# base_plate_noisy_crickets.net
KiCad netlist of a schematic drawn in EAGLE
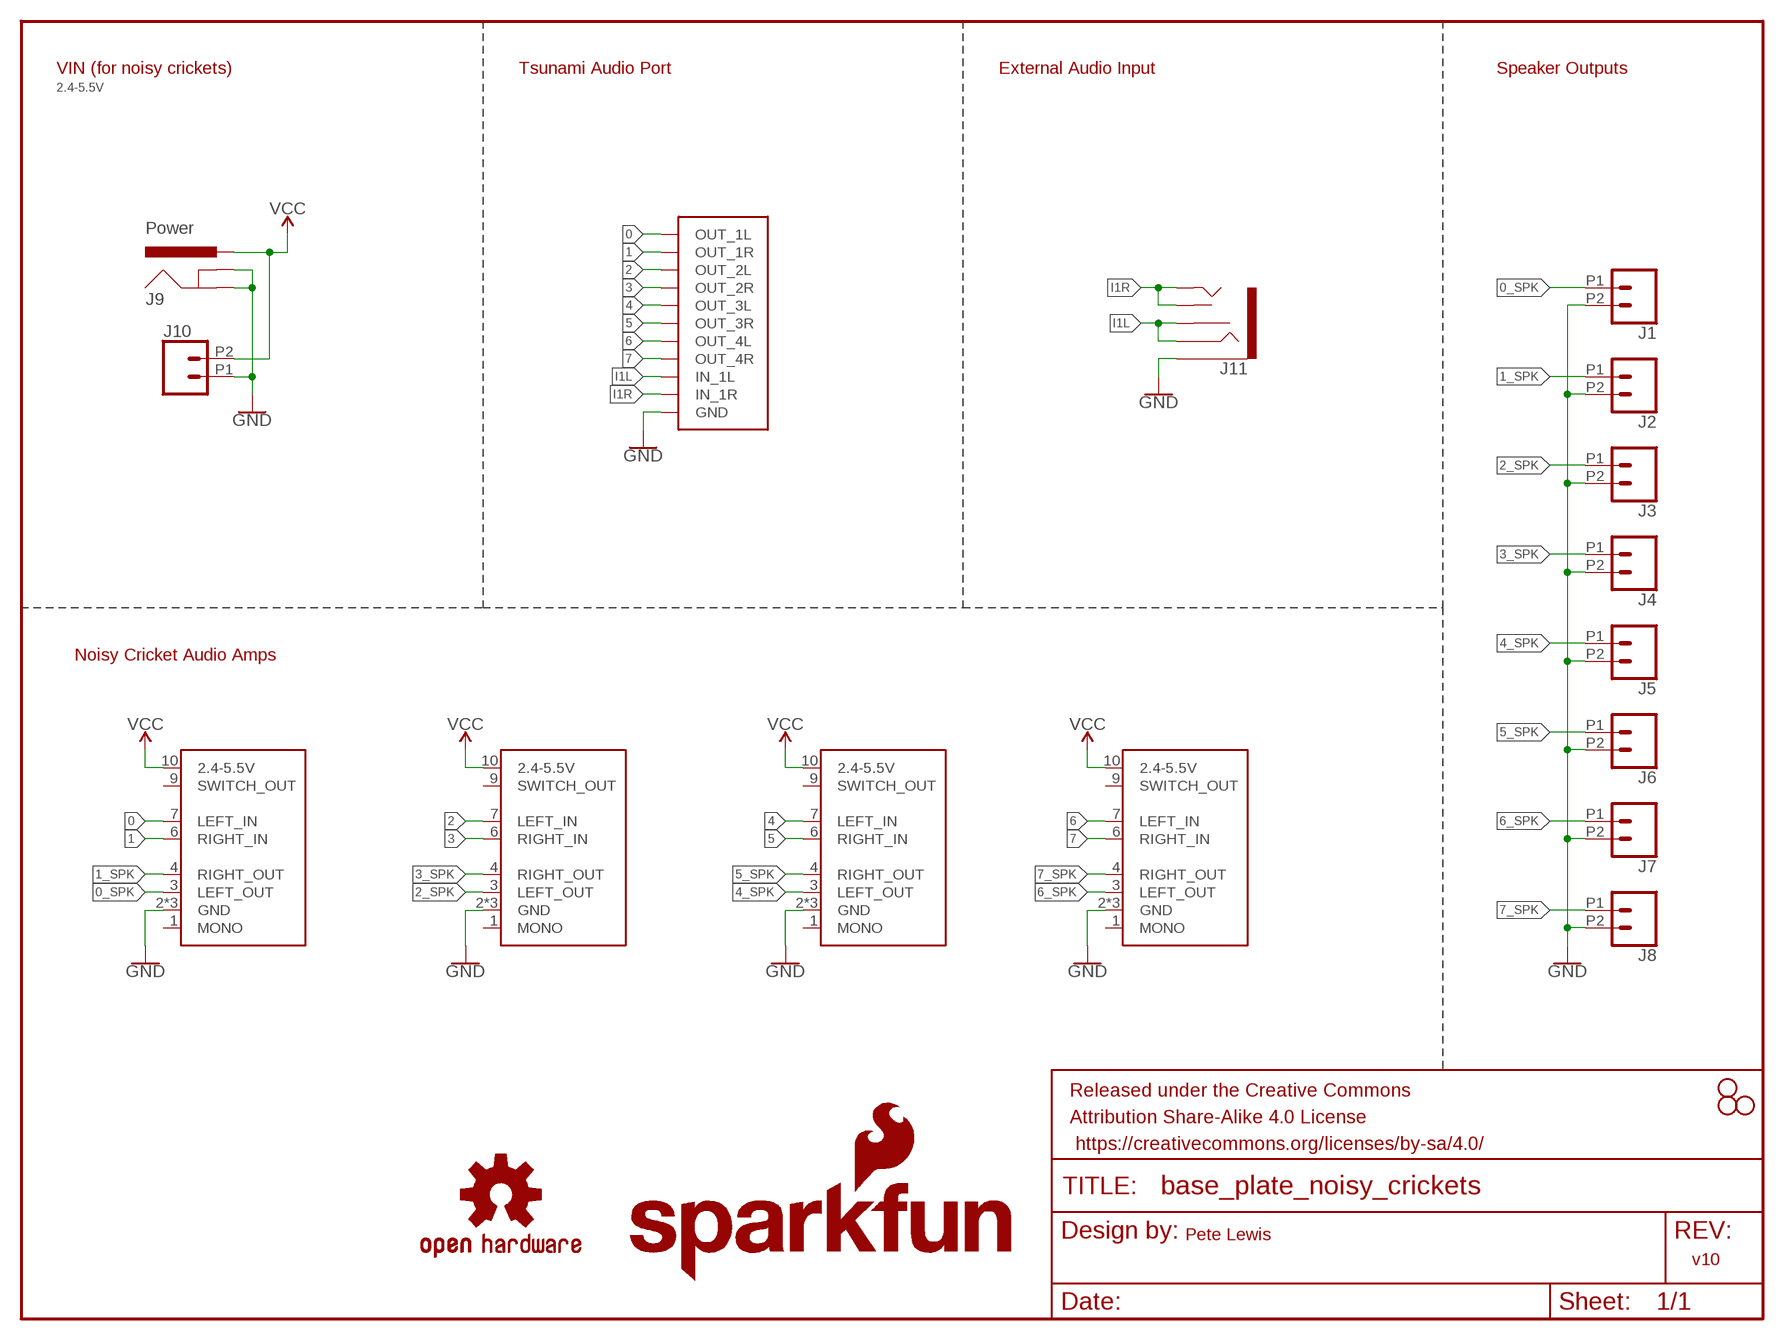
[diagram p0: schematic, sheet 1]

(export (version "E")
  (design (tool "Eeschema 10.0.6"))
  (components
    (comp (ref "FRAME1")
      (value "FRAME-LETTER")
      (footprint "eagle-import:CREATIVE_COMMONS")
      (libsource (lib "eagle-import") (part "FRAME-LETTER"))
    )
    (comp (ref "H1")
      (value "STAND-OFFTIGHT")
      (footprint "eagle-import:STAND-OFF-TIGHT")
      (libsource (lib "eagle-import") (part "STAND-OFFTIGHT"))
    )
    (comp (ref "H3")
      (value "STAND-OFFTIGHT")
      (footprint "eagle-import:STAND-OFF-TIGHT")
      (libsource (lib "eagle-import") (part "STAND-OFFTIGHT"))
    )
    (comp (ref "H4")
      (value "STAND-OFFTIGHT")
      (footprint "eagle-import:STAND-OFF-TIGHT")
      (libsource (lib "eagle-import") (part "STAND-OFFTIGHT"))
    )
    (comp (ref "J1")
      (value "CONN_022.54MM_SCREWTERM")
      (footprint "eagle-import:1X02_2.54_SCREWTERM")
      (libsource (lib "eagle-import") (part "CONN_022.54MM_SCREWTERM"))
    )
    (comp (ref "J2")
      (value "CONN_022.54MM_SCREWTERM")
      (footprint "eagle-import:1X02_2.54_SCREWTERM")
      (libsource (lib "eagle-import") (part "CONN_022.54MM_SCREWTERM"))
    )
    (comp (ref "J3")
      (value "CONN_022.54MM_SCREWTERM")
      (footprint "eagle-import:1X02_2.54_SCREWTERM")
      (libsource (lib "eagle-import") (part "CONN_022.54MM_SCREWTERM"))
    )
    (comp (ref "J4")
      (value "CONN_022.54MM_SCREWTERM")
      (footprint "eagle-import:1X02_2.54_SCREWTERM")
      (libsource (lib "eagle-import") (part "CONN_022.54MM_SCREWTERM"))
    )
    (comp (ref "J5")
      (value "CONN_022.54MM_SCREWTERM")
      (footprint "eagle-import:1X02_2.54_SCREWTERM")
      (libsource (lib "eagle-import") (part "CONN_022.54MM_SCREWTERM"))
    )
    (comp (ref "J6")
      (value "CONN_022.54MM_SCREWTERM")
      (footprint "eagle-import:1X02_2.54_SCREWTERM")
      (libsource (lib "eagle-import") (part "CONN_022.54MM_SCREWTERM"))
    )
    (comp (ref "J7")
      (value "CONN_022.54MM_SCREWTERM")
      (footprint "eagle-import:1X02_2.54_SCREWTERM")
      (libsource (lib "eagle-import") (part "CONN_022.54MM_SCREWTERM"))
    )
    (comp (ref "J8")
      (value "CONN_022.54MM_SCREWTERM")
      (footprint "eagle-import:1X02_2.54_SCREWTERM")
      (libsource (lib "eagle-import") (part "CONN_022.54MM_SCREWTERM"))
    )
    (comp (ref "J9")
      (value "Power")
      (footprint "eagle-import:POWER_JACK_PTH_LOCK")
      (libsource (lib "eagle-import") (part "POWER_JACKPTH_LOCK"))
    )
    (comp (ref "J10")
      (value "CONN_022.54MM_SCREWTERM")
      (footprint "eagle-import:1X02_2.54_SCREWTERM")
      (libsource (lib "eagle-import") (part "CONN_022.54MM_SCREWTERM"))
    )
    (comp (ref "J11")
      (value "AUDIO_JACK_3.5MM_PTH")
      (footprint "eagle-import:AUDIO-JACK")
      (libsource (lib "eagle-import") (part "AUDIO_JACK_3.5MM_PTH"))
    )
    (comp (ref "LOGO1")
      (value "SFE_LOGO_NAME_FLAME.1_INCH")
      (footprint "eagle-import:SFE_LOGO_NAME_FLAME_.1")
      (libsource (lib "eagle-import") (part "SFE_LOGO_NAME_FLAME.1_INCH"))
    )
    (comp (ref "LOGO2")
      (value "OSHW-LOGOS")
      (footprint "eagle-import:OSHW-LOGO-S")
      (libsource (lib "eagle-import") (part "OSHW-LOGOS"))
    )
    (comp (ref "LOGO3")
      (value "SFE_LOGO_NAME_FLAME.3_INCH")
      (footprint "eagle-import:SFE_LOGO_NAME_FLAME_.3")
      (libsource (lib "eagle-import") (part "SFE_LOGO_NAME_FLAME.3_INCH"))
    )
    (comp (ref "U$1")
      (value "NOISY_CRICKET")
      (footprint "eagle-import:NOISY_CRICKET_W_PTH")
      (libsource (lib "eagle-import") (part "NOISY_CRICKET"))
    )
    (comp (ref "U$2")
      (value "NOISY_CRICKET")
      (footprint "eagle-import:NOISY_CRICKET_W_PTH")
      (libsource (lib "eagle-import") (part "NOISY_CRICKET"))
    )
    (comp (ref "U$3")
      (value "NOISY_CRICKET")
      (footprint "eagle-import:NOISY_CRICKET_W_PTH")
      (libsource (lib "eagle-import") (part "NOISY_CRICKET"))
    )
    (comp (ref "U$4")
      (value "NOISY_CRICKET")
      (footprint "eagle-import:NOISY_CRICKET_W_PTH")
      (libsource (lib "eagle-import") (part "NOISY_CRICKET"))
    )
    (comp (ref "U$5")
      (value "TSUNAMI_AUDIO_PORTS")
      (footprint "eagle-import:TSUNAMI_AUDIO_PORTS")
      (libsource (lib "eagle-import") (part "TSUNAMI_AUDIO_PORTS"))
    )
  )
  (nets
    (net (code "1") (name "0") (class "Default")
      (node (ref "U$1") (pin "7") (pinfunction "LEFT_IN_7") (pintype "bidirectional"))
      (node (ref "U$5") (pin "O1L") (pinfunction "OUT_1L_O1L") (pintype "bidirectional"))
    )
    (net (code "2") (name "0_SPK") (class "Default")
      (node (ref "J1") (pin "P1") (pinfunction "1_P1") (pintype "passive"))
      (node (ref "U$1") (pin "3") (pinfunction "LEFT_OUT_3") (pintype "bidirectional"))
    )
    (net (code "3") (name "1") (class "Default")
      (node (ref "U$1") (pin "6") (pinfunction "RIGHT_IN_6") (pintype "bidirectional"))
      (node (ref "U$5") (pin "O1R") (pinfunction "OUT_1R_O1R") (pintype "bidirectional"))
    )
    (net (code "4") (name "1_SPK") (class "Default")
      (node (ref "J2") (pin "P1") (pinfunction "1_P1") (pintype "passive"))
      (node (ref "U$1") (pin "4") (pinfunction "RIGHT_OUT_4") (pintype "bidirectional"))
    )
    (net (code "5") (name "2") (class "Default")
      (node (ref "U$2") (pin "7") (pinfunction "LEFT_IN_7") (pintype "bidirectional"))
      (node (ref "U$5") (pin "O2L") (pinfunction "OUT_2L_O2L") (pintype "bidirectional"))
    )
    (net (code "6") (name "2_SPK") (class "Default")
      (node (ref "J3") (pin "P1") (pinfunction "1_P1") (pintype "passive"))
      (node (ref "U$2") (pin "3") (pinfunction "LEFT_OUT_3") (pintype "bidirectional"))
    )
    (net (code "7") (name "3") (class "Default")
      (node (ref "U$2") (pin "6") (pinfunction "RIGHT_IN_6") (pintype "bidirectional"))
      (node (ref "U$5") (pin "O2R") (pinfunction "OUT_2R_O2R") (pintype "bidirectional"))
    )
    (net (code "8") (name "3_SPK") (class "Default")
      (node (ref "J4") (pin "P1") (pinfunction "1_P1") (pintype "passive"))
      (node (ref "U$2") (pin "4") (pinfunction "RIGHT_OUT_4") (pintype "bidirectional"))
    )
    (net (code "9") (name "4") (class "Default")
      (node (ref "U$3") (pin "7") (pinfunction "LEFT_IN_7") (pintype "bidirectional"))
      (node (ref "U$5") (pin "O3L") (pinfunction "OUT_3L_O3L") (pintype "bidirectional"))
    )
    (net (code "10") (name "4_SPK") (class "Default")
      (node (ref "J5") (pin "P1") (pinfunction "1_P1") (pintype "passive"))
      (node (ref "U$3") (pin "3") (pinfunction "LEFT_OUT_3") (pintype "bidirectional"))
    )
    (net (code "11") (name "5") (class "Default")
      (node (ref "U$3") (pin "6") (pinfunction "RIGHT_IN_6") (pintype "bidirectional"))
      (node (ref "U$5") (pin "O3R") (pinfunction "OUT_3R_O3R") (pintype "bidirectional"))
    )
    (net (code "12") (name "5_SPK") (class "Default")
      (node (ref "J6") (pin "P1") (pinfunction "1_P1") (pintype "passive"))
      (node (ref "U$3") (pin "4") (pinfunction "RIGHT_OUT_4") (pintype "bidirectional"))
    )
    (net (code "13") (name "6") (class "Default")
      (node (ref "U$4") (pin "7") (pinfunction "LEFT_IN_7") (pintype "bidirectional"))
      (node (ref "U$5") (pin "O4L") (pinfunction "OUT_4L_O4L") (pintype "bidirectional"))
    )
    (net (code "14") (name "6_SPK") (class "Default")
      (node (ref "J7") (pin "P1") (pinfunction "1_P1") (pintype "passive"))
      (node (ref "U$4") (pin "3") (pinfunction "LEFT_OUT_3") (pintype "bidirectional"))
    )
    (net (code "15") (name "7") (class "Default")
      (node (ref "U$4") (pin "6") (pinfunction "RIGHT_IN_6") (pintype "bidirectional"))
      (node (ref "U$5") (pin "O4R") (pinfunction "OUT_4R_O4R") (pintype "bidirectional"))
    )
    (net (code "16") (name "7_SPK") (class "Default")
      (node (ref "J8") (pin "P1") (pinfunction "1_P1") (pintype "passive"))
      (node (ref "U$4") (pin "4") (pinfunction "RIGHT_OUT_4") (pintype "bidirectional"))
    )
    (net (code "17") (name "GND") (class "Default")
      (node (ref "J1") (pin "P2") (pinfunction "2_P2") (pintype "passive"))
      (node (ref "J10") (pin "P1") (pinfunction "1_P1") (pintype "passive"))
      (node (ref "J11") (pin "SLEEVE") (pinfunction "SLEEVE_SLEEVE") (pintype "bidirectional"))
      (node (ref "J2") (pin "P2") (pinfunction "2_P2") (pintype "passive"))
      (node (ref "J3") (pin "P2") (pinfunction "2_P2") (pintype "passive"))
      (node (ref "J4") (pin "P2") (pinfunction "2_P2") (pintype "passive"))
      (node (ref "J5") (pin "P2") (pinfunction "2_P2") (pintype "passive"))
      (node (ref "J6") (pin "P2") (pinfunction "2_P2") (pintype "passive"))
      (node (ref "J7") (pin "P2") (pinfunction "2_P2") (pintype "passive"))
      (node (ref "J8") (pin "P2") (pinfunction "2_P2") (pintype "passive"))
      (node (ref "J9") (pin "GND") (pinfunction "GND_GND") (pintype "bidirectional"))
      (node (ref "J9") (pin "GNDBREAK") (pinfunction "GNDBREAK_GNDBREAK") (pintype "bidirectional"))
      (node (ref "U$1") (pin "2") (pinfunction "GND_2") (pintype "bidirectional"))
      (node (ref "U$1") (pin "5") (pinfunction "GND_5") (pintype "bidirectional"))
      (node (ref "U$1") (pin "8") (pinfunction "GND_8") (pintype "bidirectional"))
      (node (ref "U$2") (pin "2") (pinfunction "GND_2") (pintype "bidirectional"))
      (node (ref "U$2") (pin "5") (pinfunction "GND_5") (pintype "bidirectional"))
      (node (ref "U$2") (pin "8") (pinfunction "GND_8") (pintype "bidirectional"))
      (node (ref "U$3") (pin "2") (pinfunction "GND_2") (pintype "bidirectional"))
      (node (ref "U$3") (pin "5") (pinfunction "GND_5") (pintype "bidirectional"))
      (node (ref "U$3") (pin "8") (pinfunction "GND_8") (pintype "bidirectional"))
      (node (ref "U$4") (pin "2") (pinfunction "GND_2") (pintype "bidirectional"))
      (node (ref "U$4") (pin "5") (pinfunction "GND_5") (pintype "bidirectional"))
      (node (ref "U$4") (pin "8") (pinfunction "GND_8") (pintype "bidirectional"))
      (node (ref "U$5") (pin "P$11") (pinfunction "GND_P$11") (pintype "bidirectional"))
      (node (ref "U$5") (pin "P$12") (pinfunction "GND_P$12") (pintype "bidirectional"))
      (node (ref "U$5") (pin "P$13") (pinfunction "GND_P$13") (pintype "bidirectional"))
      (node (ref "U$5") (pin "P$14") (pinfunction "GND_P$14") (pintype "bidirectional"))
      (node (ref "U$5") (pin "P$15") (pinfunction "GND_P$15") (pintype "bidirectional"))
      (node (ref "U$5") (pin "P$16") (pinfunction "GND_P$16") (pintype "bidirectional"))
      (node (ref "U$5") (pin "P$17") (pinfunction "GND_P$17") (pintype "bidirectional"))
      (node (ref "U$5") (pin "P$18") (pinfunction "GND_P$18") (pintype "bidirectional"))
      (node (ref "U$5") (pin "P$19") (pinfunction "GND_P$19") (pintype "bidirectional"))
      (node (ref "U$5") (pin "P$20") (pinfunction "GND_P$20") (pintype "bidirectional"))
    )
    (net (code "18") (name "I1L") (class "Default")
      (node (ref "J11") (pin "RING") (pinfunction "RING_RING") (pintype "bidirectional"))
      (node (ref "J11") (pin "RSH") (pinfunction "RSH_RSH") (pintype "bidirectional"))
      (node (ref "U$5") (pin "I1L") (pinfunction "IN_1L_I1L") (pintype "bidirectional"))
    )
    (net (code "19") (name "I1R") (class "Default")
      (node (ref "J11") (pin "TIP") (pinfunction "TIP_TIP") (pintype "bidirectional"))
      (node (ref "J11") (pin "TSH") (pinfunction "TSH_TSH") (pintype "bidirectional"))
      (node (ref "U$5") (pin "I1R") (pinfunction "IN_1R_I1R") (pintype "bidirectional"))
    )
    (net (code "20") (name "VCC") (class "Default")
      (node (ref "J10") (pin "P2") (pinfunction "2_P2") (pintype "passive"))
      (node (ref "J9") (pin "PWR") (pinfunction "PWR_PWR") (pintype "bidirectional"))
      (node (ref "U$1") (pin "10") (pinfunction "2.4-5.5V_10") (pintype "bidirectional"))
      (node (ref "U$2") (pin "10") (pinfunction "2.4-5.5V_10") (pintype "bidirectional"))
      (node (ref "U$3") (pin "10") (pinfunction "2.4-5.5V_10") (pintype "bidirectional"))
      (node (ref "U$4") (pin "10") (pinfunction "2.4-5.5V_10") (pintype "bidirectional"))
    )
    (net (code "21") (name "unconnected-(U$1-MONO-Pad1)") (class "Default")
      (node (ref "U$1") (pin "1") (pinfunction "MONO_1") (pintype "bidirectional"))
    )
    (net (code "22") (name "unconnected-(U$1-SWITCH_OUT-Pad9)") (class "Default")
      (node (ref "U$1") (pin "9") (pinfunction "SWITCH_OUT_9") (pintype "bidirectional"))
    )
    (net (code "23") (name "unconnected-(U$2-MONO-Pad1)") (class "Default")
      (node (ref "U$2") (pin "1") (pinfunction "MONO_1") (pintype "bidirectional"))
    )
    (net (code "24") (name "unconnected-(U$2-SWITCH_OUT-Pad9)") (class "Default")
      (node (ref "U$2") (pin "9") (pinfunction "SWITCH_OUT_9") (pintype "bidirectional"))
    )
    (net (code "25") (name "unconnected-(U$3-MONO-Pad1)") (class "Default")
      (node (ref "U$3") (pin "1") (pinfunction "MONO_1") (pintype "bidirectional"))
    )
    (net (code "26") (name "unconnected-(U$3-SWITCH_OUT-Pad9)") (class "Default")
      (node (ref "U$3") (pin "9") (pinfunction "SWITCH_OUT_9") (pintype "bidirectional"))
    )
    (net (code "27") (name "unconnected-(U$4-MONO-Pad1)") (class "Default")
      (node (ref "U$4") (pin "1") (pinfunction "MONO_1") (pintype "bidirectional"))
    )
    (net (code "28") (name "unconnected-(U$4-SWITCH_OUT-Pad9)") (class "Default")
      (node (ref "U$4") (pin "9") (pinfunction "SWITCH_OUT_9") (pintype "bidirectional"))
    )
  )
)
